# 4_x_4_block.net
KiCad netlist of a schematic drawn in EAGLE
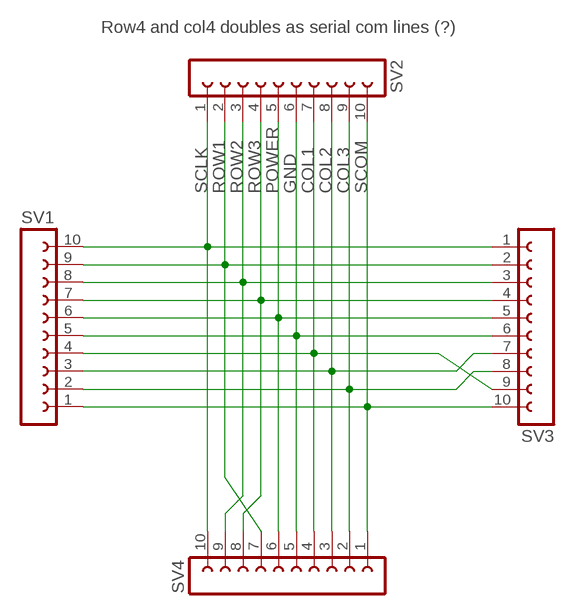
[diagram p0: schematic, sheet 1]

(export (version "E")
  (design (tool "Eeschema 10.0.6"))
  (components
    (comp (ref "SV1")
      (value "FE10-1")
      (footprint "eagle-import:FE10")
      (libsource (lib "eagle-import") (part "FE10-1"))
    )
    (comp (ref "SV2")
      (value "FE10-1")
      (footprint "eagle-import:FE10")
      (libsource (lib "eagle-import") (part "FE10-1"))
    )
    (comp (ref "SV3")
      (value "FE10-1")
      (footprint "eagle-import:FE10")
      (libsource (lib "eagle-import") (part "FE10-1"))
    )
    (comp (ref "SV4")
      (value "FE10-1")
      (footprint "eagle-import:FE10")
      (libsource (lib "eagle-import") (part "FE10-1"))
    )
  )
  (nets
    (net (code "1") (name "/COL1") (class "Default")
      (node (ref "SV1") (pin "4") (pinfunction "4_4") (pintype "passive"))
      (node (ref "SV2") (pin "7") (pinfunction "7_7") (pintype "passive"))
      (node (ref "SV3") (pin "9") (pinfunction "9_9") (pintype "passive"))
      (node (ref "SV4") (pin "4") (pinfunction "4_4") (pintype "passive"))
    )
    (net (code "2") (name "/COL2") (class "Default")
      (node (ref "SV1") (pin "3") (pinfunction "3_3") (pintype "passive"))
      (node (ref "SV2") (pin "8") (pinfunction "8_8") (pintype "passive"))
      (node (ref "SV3") (pin "7") (pinfunction "7_7") (pintype "passive"))
      (node (ref "SV4") (pin "3") (pinfunction "3_3") (pintype "passive"))
    )
    (net (code "3") (name "/COL3") (class "Default")
      (node (ref "SV1") (pin "2") (pinfunction "2_2") (pintype "passive"))
      (node (ref "SV2") (pin "9") (pinfunction "9_9") (pintype "passive"))
      (node (ref "SV3") (pin "8") (pinfunction "8_8") (pintype "passive"))
      (node (ref "SV4") (pin "2") (pinfunction "2_2") (pintype "passive"))
    )
    (net (code "4") (name "/GND") (class "Default")
      (node (ref "SV1") (pin "5") (pinfunction "5_5") (pintype "passive"))
      (node (ref "SV2") (pin "6") (pinfunction "6_6") (pintype "passive"))
      (node (ref "SV3") (pin "6") (pinfunction "6_6") (pintype "passive"))
      (node (ref "SV4") (pin "5") (pinfunction "5_5") (pintype "passive"))
    )
    (net (code "5") (name "/POWER") (class "Default")
      (node (ref "SV1") (pin "6") (pinfunction "6_6") (pintype "passive"))
      (node (ref "SV2") (pin "5") (pinfunction "5_5") (pintype "passive"))
      (node (ref "SV3") (pin "5") (pinfunction "5_5") (pintype "passive"))
      (node (ref "SV4") (pin "6") (pinfunction "6_6") (pintype "passive"))
    )
    (net (code "6") (name "/ROW1") (class "Default")
      (node (ref "SV1") (pin "9") (pinfunction "9_9") (pintype "passive"))
      (node (ref "SV2") (pin "2") (pinfunction "2_2") (pintype "passive"))
      (node (ref "SV3") (pin "2") (pinfunction "2_2") (pintype "passive"))
      (node (ref "SV4") (pin "7") (pinfunction "7_7") (pintype "passive"))
    )
    (net (code "7") (name "/ROW2") (class "Default")
      (node (ref "SV1") (pin "8") (pinfunction "8_8") (pintype "passive"))
      (node (ref "SV2") (pin "3") (pinfunction "3_3") (pintype "passive"))
      (node (ref "SV3") (pin "3") (pinfunction "3_3") (pintype "passive"))
      (node (ref "SV4") (pin "9") (pinfunction "9_9") (pintype "passive"))
    )
    (net (code "8") (name "/ROW3") (class "Default")
      (node (ref "SV1") (pin "7") (pinfunction "7_7") (pintype "passive"))
      (node (ref "SV2") (pin "4") (pinfunction "4_4") (pintype "passive"))
      (node (ref "SV3") (pin "4") (pinfunction "4_4") (pintype "passive"))
      (node (ref "SV4") (pin "8") (pinfunction "8_8") (pintype "passive"))
    )
    (net (code "9") (name "/SCLK") (class "Default")
      (node (ref "SV1") (pin "10") (pinfunction "10_10") (pintype "passive"))
      (node (ref "SV2") (pin "1") (pinfunction "1_1") (pintype "passive"))
      (node (ref "SV3") (pin "1") (pinfunction "1_1") (pintype "passive"))
      (node (ref "SV4") (pin "10") (pinfunction "10_10") (pintype "passive"))
    )
    (net (code "10") (name "/SCOM") (class "Default")
      (node (ref "SV1") (pin "1") (pinfunction "1_1") (pintype "passive"))
      (node (ref "SV2") (pin "10") (pinfunction "10_10") (pintype "passive"))
      (node (ref "SV3") (pin "10") (pinfunction "10_10") (pintype "passive"))
      (node (ref "SV4") (pin "1") (pinfunction "1_1") (pintype "passive"))
    )
  )
)
